# BitBeacon.net
KiCad netlist of a schematic drawn in EAGLE
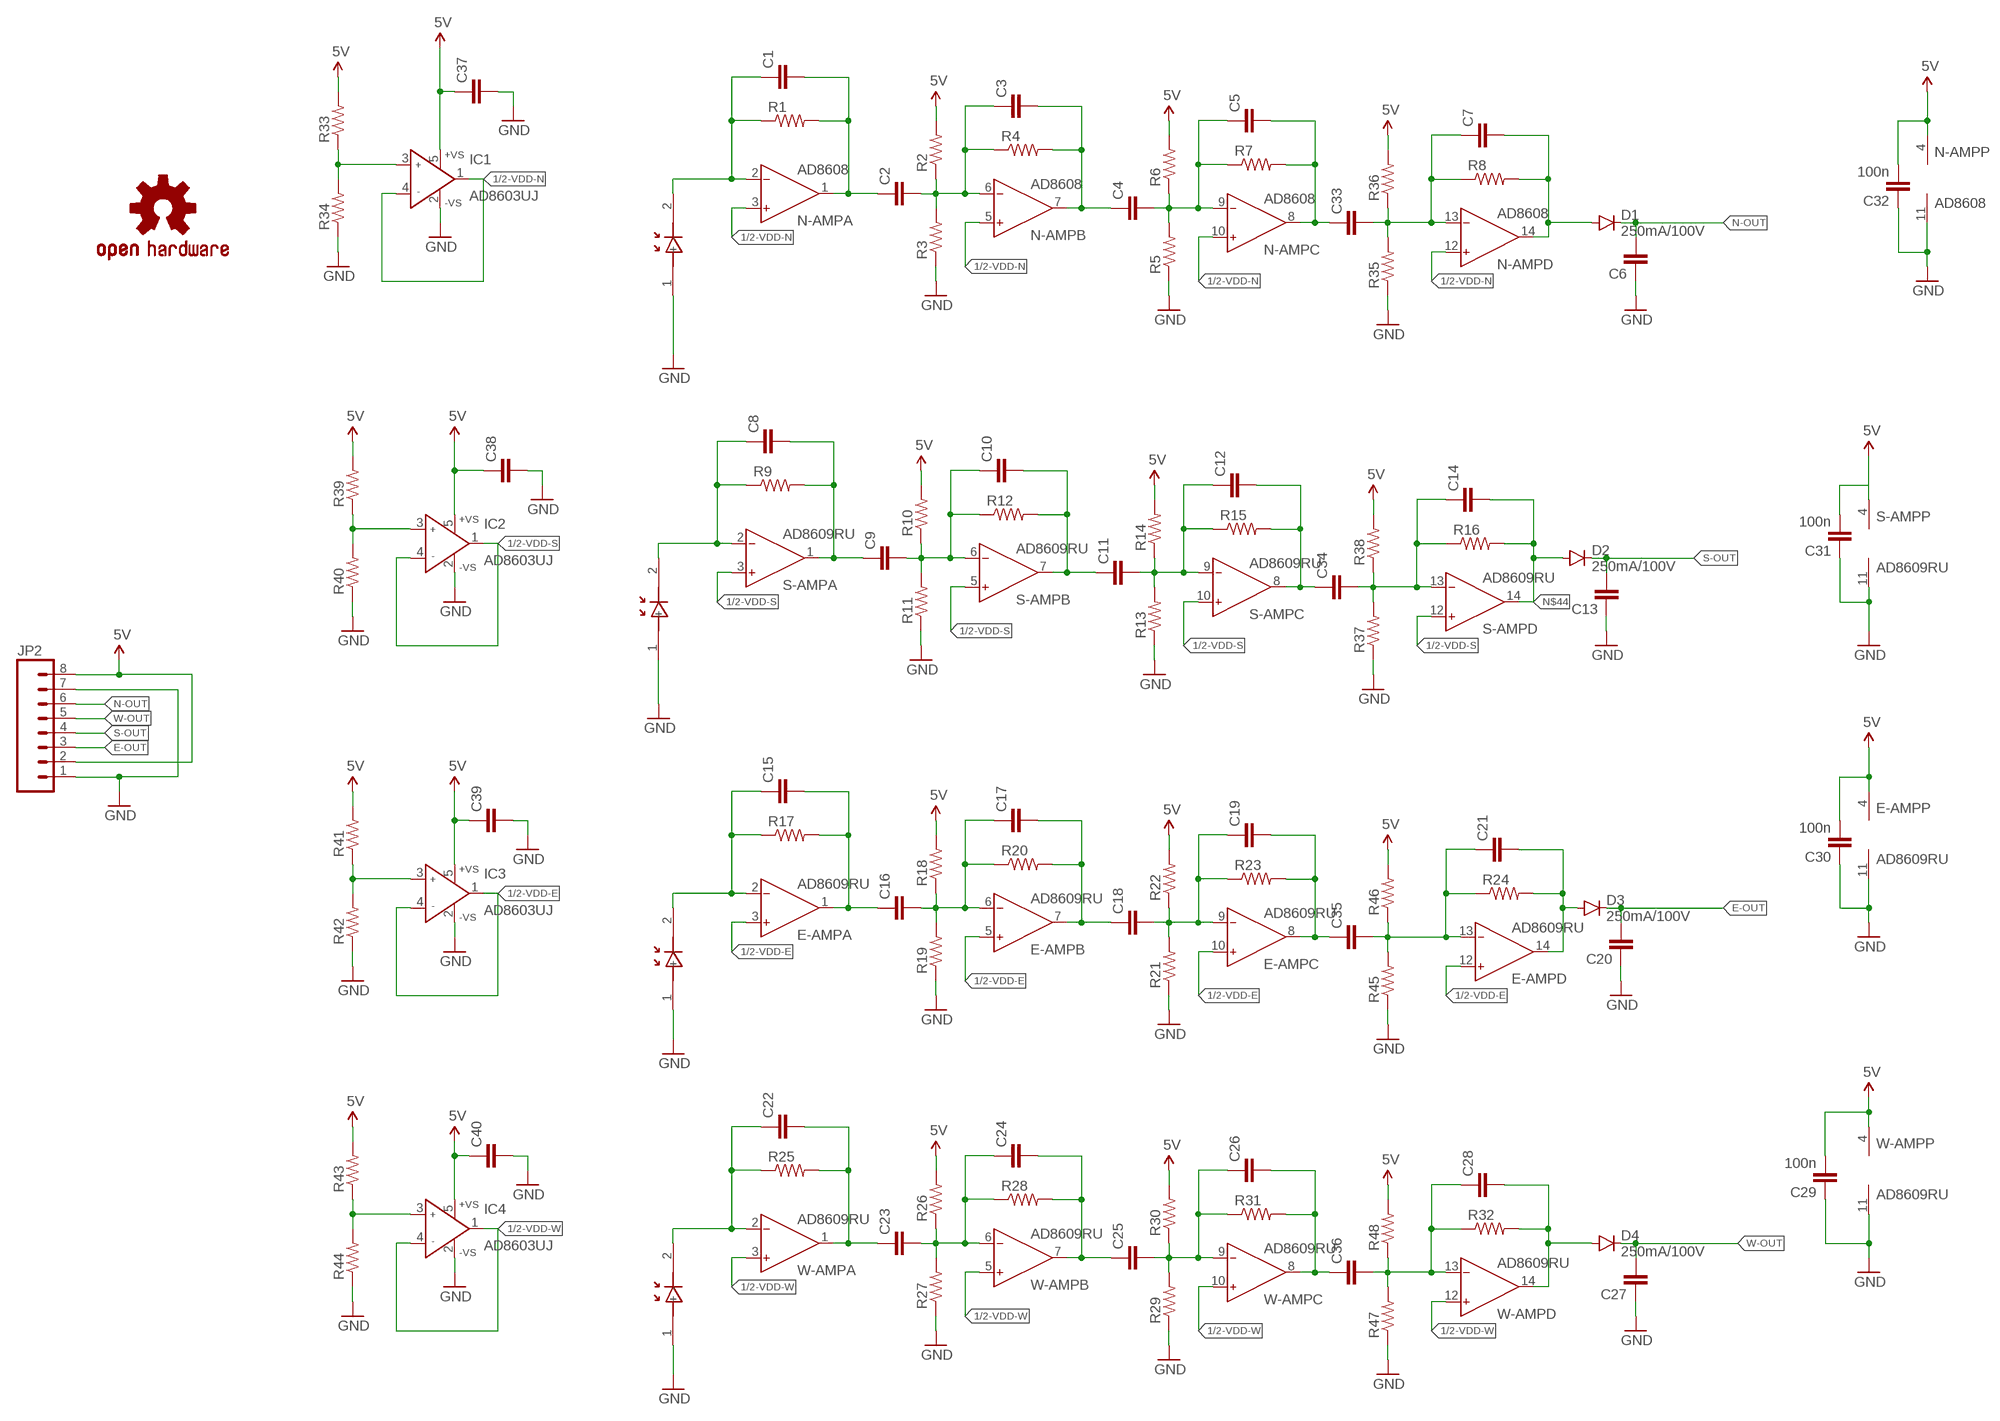
[diagram p0: schematic, sheet 1]

(export (version "E")
  (design (tool "Eeschema 10.0.6"))
  (components
    (comp (ref "C1")
      (value "C-EUC0402")
      (footprint "eagle-import:C0402")
      (libsource (lib "eagle-import") (part "C-EUC0402"))
    )
    (comp (ref "C2")
      (value "C-EUC0402")
      (footprint "eagle-import:C0402")
      (libsource (lib "eagle-import") (part "C-EUC0402"))
    )
    (comp (ref "C3")
      (value "C-EUC0402")
      (footprint "eagle-import:C0402")
      (libsource (lib "eagle-import") (part "C-EUC0402"))
    )
    (comp (ref "C4")
      (value "C-EUC0402")
      (footprint "eagle-import:C0402")
      (libsource (lib "eagle-import") (part "C-EUC0402"))
    )
    (comp (ref "C5")
      (value "C-EUC0402")
      (footprint "eagle-import:C0402")
      (libsource (lib "eagle-import") (part "C-EUC0402"))
    )
    (comp (ref "C6")
      (value "C-EUC0402")
      (footprint "eagle-import:C0402")
      (libsource (lib "eagle-import") (part "C-EUC0402"))
    )
    (comp (ref "C7")
      (value "C-EUC0402")
      (footprint "eagle-import:C0402")
      (libsource (lib "eagle-import") (part "C-EUC0402"))
    )
    (comp (ref "C8")
      (value "C-EUC0402")
      (footprint "eagle-import:C0402")
      (libsource (lib "eagle-import") (part "C-EUC0402"))
    )
    (comp (ref "C9")
      (value "C-EUC0402")
      (footprint "eagle-import:C0402")
      (libsource (lib "eagle-import") (part "C-EUC0402"))
    )
    (comp (ref "C10")
      (value "C-EUC0402")
      (footprint "eagle-import:C0402")
      (libsource (lib "eagle-import") (part "C-EUC0402"))
    )
    (comp (ref "C11")
      (value "C-EUC0402")
      (footprint "eagle-import:C0402")
      (libsource (lib "eagle-import") (part "C-EUC0402"))
    )
    (comp (ref "C12")
      (value "C-EUC0402")
      (footprint "eagle-import:C0402")
      (libsource (lib "eagle-import") (part "C-EUC0402"))
    )
    (comp (ref "C13")
      (value "C-EUC0402")
      (footprint "eagle-import:C0402")
      (libsource (lib "eagle-import") (part "C-EUC0402"))
    )
    (comp (ref "C14")
      (value "C-EUC0402")
      (footprint "eagle-import:C0402")
      (libsource (lib "eagle-import") (part "C-EUC0402"))
    )
    (comp (ref "C15")
      (value "C-EUC0402")
      (footprint "eagle-import:C0402")
      (libsource (lib "eagle-import") (part "C-EUC0402"))
    )
    (comp (ref "C16")
      (value "C-EUC0402")
      (footprint "eagle-import:C0402")
      (libsource (lib "eagle-import") (part "C-EUC0402"))
    )
    (comp (ref "C17")
      (value "C-EUC0402")
      (footprint "eagle-import:C0402")
      (libsource (lib "eagle-import") (part "C-EUC0402"))
    )
    (comp (ref "C18")
      (value "C-EUC0402")
      (footprint "eagle-import:C0402")
      (libsource (lib "eagle-import") (part "C-EUC0402"))
    )
    (comp (ref "C19")
      (value "C-EUC0402")
      (footprint "eagle-import:C0402")
      (libsource (lib "eagle-import") (part "C-EUC0402"))
    )
    (comp (ref "C20")
      (value "C-EUC0402")
      (footprint "eagle-import:C0402")
      (libsource (lib "eagle-import") (part "C-EUC0402"))
    )
    (comp (ref "C21")
      (value "C-EUC0402")
      (footprint "eagle-import:C0402")
      (libsource (lib "eagle-import") (part "C-EUC0402"))
    )
    (comp (ref "C22")
      (value "C-EUC0402")
      (footprint "eagle-import:C0402")
      (libsource (lib "eagle-import") (part "C-EUC0402"))
    )
    (comp (ref "C23")
      (value "C-EUC0402")
      (footprint "eagle-import:C0402")
      (libsource (lib "eagle-import") (part "C-EUC0402"))
    )
    (comp (ref "C24")
      (value "C-EUC0402")
      (footprint "eagle-import:C0402")
      (libsource (lib "eagle-import") (part "C-EUC0402"))
    )
    (comp (ref "C25")
      (value "C-EUC0402")
      (footprint "eagle-import:C0402")
      (libsource (lib "eagle-import") (part "C-EUC0402"))
    )
    (comp (ref "C26")
      (value "C-EUC0402")
      (footprint "eagle-import:C0402")
      (libsource (lib "eagle-import") (part "C-EUC0402"))
    )
    (comp (ref "C27")
      (value "C-EUC0402")
      (footprint "eagle-import:C0402")
      (libsource (lib "eagle-import") (part "C-EUC0402"))
    )
    (comp (ref "C28")
      (value "C-EUC0402")
      (footprint "eagle-import:C0402")
      (libsource (lib "eagle-import") (part "C-EUC0402"))
    )
    (comp (ref "C29")
      (value "100n")
      (footprint "eagle-import:C0402")
      (libsource (lib "eagle-import") (part "C-EUC0402"))
    )
    (comp (ref "C30")
      (value "100n")
      (footprint "eagle-import:C0402")
      (libsource (lib "eagle-import") (part "C-EUC0402"))
    )
    (comp (ref "C31")
      (value "100n")
      (footprint "eagle-import:C0402")
      (libsource (lib "eagle-import") (part "C-EUC0402"))
    )
    (comp (ref "C32")
      (value "100n")
      (footprint "eagle-import:C0402")
      (libsource (lib "eagle-import") (part "C-EUC0402"))
    )
    (comp (ref "C33")
      (value "C-EUC0402")
      (footprint "eagle-import:C0402")
      (libsource (lib "eagle-import") (part "C-EUC0402"))
    )
    (comp (ref "C34")
      (value "C-EUC0402")
      (footprint "eagle-import:C0402")
      (libsource (lib "eagle-import") (part "C-EUC0402"))
    )
    (comp (ref "C35")
      (value "C-EUC0402")
      (footprint "eagle-import:C0402")
      (libsource (lib "eagle-import") (part "C-EUC0402"))
    )
    (comp (ref "C36")
      (value "C-EUC0402")
      (footprint "eagle-import:C0402")
      (libsource (lib "eagle-import") (part "C-EUC0402"))
    )
    (comp (ref "C37")
      (value "C-EUC0402")
      (footprint "eagle-import:C0402")
      (libsource (lib "eagle-import") (part "C-EUC0402"))
    )
    (comp (ref "C38")
      (value "C-EUC0402")
      (footprint "eagle-import:C0402")
      (libsource (lib "eagle-import") (part "C-EUC0402"))
    )
    (comp (ref "C39")
      (value "C-EUC0402")
      (footprint "eagle-import:C0402")
      (libsource (lib "eagle-import") (part "C-EUC0402"))
    )
    (comp (ref "C40")
      (value "C-EUC0402")
      (footprint "eagle-import:C0402")
      (libsource (lib "eagle-import") (part "C-EUC0402"))
    )
    (comp (ref "D1")
      (value "250mA/100V")
      (footprint "eagle-import:SOD-323")
      (libsource (lib "eagle-import") (part "DIODEBAS16"))
    )
    (comp (ref "D2")
      (value "250mA/100V")
      (footprint "eagle-import:SOD-323")
      (libsource (lib "eagle-import") (part "DIODEBAS16"))
    )
    (comp (ref "D3")
      (value "250mA/100V")
      (footprint "eagle-import:SOD-323")
      (libsource (lib "eagle-import") (part "DIODEBAS16"))
    )
    (comp (ref "D4")
      (value "250mA/100V")
      (footprint "eagle-import:SOD-323")
      (libsource (lib "eagle-import") (part "DIODEBAS16"))
    )
    (comp (ref "E-AMP")
      (value "AD8609RU")
      (footprint "eagle-import:TSSOP14")
      (fields (field (name "MF") "ALTERA CORPORATION") (field (name "MPN") "AD8609ARUZ"))
      (libsource (lib "eagle-import") (part "AD8609RU"))
    )
    (comp (ref "E-PD1")
      (value "BPW46")
      (footprint "eagle-import:PIN-PHOTODIODE")
      (libsource (lib "eagle-import") (part "BPW46"))
    )
    (comp (ref "IC1")
      (value "AD8603UJ")
      (footprint "eagle-import:SOT23-5")
      (fields (field (name "MF") "ALTERA CORPORATION") (field (name "MPN") "AD8603AUJZ-REEL7"))
      (libsource (lib "eagle-import") (part "AD8603UJ"))
    )
    (comp (ref "IC2")
      (value "AD8603UJ")
      (footprint "eagle-import:SOT23-5")
      (fields (field (name "MF") "ALTERA CORPORATION") (field (name "MPN") "AD8603AUJZ-REEL7"))
      (libsource (lib "eagle-import") (part "AD8603UJ"))
    )
    (comp (ref "IC3")
      (value "AD8603UJ")
      (footprint "eagle-import:SOT23-5")
      (fields (field (name "MF") "ALTERA CORPORATION") (field (name "MPN") "AD8603AUJZ-REEL7"))
      (libsource (lib "eagle-import") (part "AD8603UJ"))
    )
    (comp (ref "IC4")
      (value "AD8603UJ")
      (footprint "eagle-import:SOT23-5")
      (fields (field (name "MF") "ALTERA CORPORATION") (field (name "MPN") "AD8603AUJZ-REEL7"))
      (libsource (lib "eagle-import") (part "AD8603UJ"))
    )
    (comp (ref "JP2")
      (value "M08NO_SILK")
      (footprint "eagle-import:1X08_PIN1_NO_SILK")
      (libsource (lib "eagle-import") (part "M08NO_SILK"))
    )
    (comp (ref "LOGO1")
      (value "OSHW-LOGOS")
      (footprint "eagle-import:OSHW-LOGO-S")
      (libsource (lib "eagle-import") (part "OSHW-LOGOS"))
    )
    (comp (ref "N-AMP")
      (value "AD8608")
      (footprint "eagle-import:TSSOP14")
      (fields (field (name "MF") "ALTERA CORPORATION") (field (name "MPN") "AD8609ARUZ"))
      (libsource (lib "eagle-import") (part "AD8609RU"))
    )
    (comp (ref "N-PD1")
      (value "BPW46")
      (footprint "eagle-import:PIN-PHOTODIODE")
      (libsource (lib "eagle-import") (part "BPW46"))
    )
    (comp (ref "R1")
      (value "R-US_R0402")
      (footprint "eagle-import:R0402")
      (libsource (lib "eagle-import") (part "R-US_R0402"))
    )
    (comp (ref "R2")
      (value "R-US_R0402")
      (footprint "eagle-import:R0402")
      (libsource (lib "eagle-import") (part "R-US_R0402"))
    )
    (comp (ref "R3")
      (value "R-US_R0402")
      (footprint "eagle-import:R0402")
      (libsource (lib "eagle-import") (part "R-US_R0402"))
    )
    (comp (ref "R4")
      (value "R-US_R0402")
      (footprint "eagle-import:R0402")
      (libsource (lib "eagle-import") (part "R-US_R0402"))
    )
    (comp (ref "R5")
      (value "R-US_R0402")
      (footprint "eagle-import:R0402")
      (libsource (lib "eagle-import") (part "R-US_R0402"))
    )
    (comp (ref "R6")
      (value "R-US_R0402")
      (footprint "eagle-import:R0402")
      (libsource (lib "eagle-import") (part "R-US_R0402"))
    )
    (comp (ref "R7")
      (value "R-US_R0402")
      (footprint "eagle-import:R0402")
      (libsource (lib "eagle-import") (part "R-US_R0402"))
    )
    (comp (ref "R8")
      (value "R-US_R0402")
      (footprint "eagle-import:R0402")
      (libsource (lib "eagle-import") (part "R-US_R0402"))
    )
    (comp (ref "R9")
      (value "R-US_R0402")
      (footprint "eagle-import:R0402")
      (libsource (lib "eagle-import") (part "R-US_R0402"))
    )
    (comp (ref "R10")
      (value "R-US_R0402")
      (footprint "eagle-import:R0402")
      (libsource (lib "eagle-import") (part "R-US_R0402"))
    )
    (comp (ref "R11")
      (value "R-US_R0402")
      (footprint "eagle-import:R0402")
      (libsource (lib "eagle-import") (part "R-US_R0402"))
    )
    (comp (ref "R12")
      (value "R-US_R0402")
      (footprint "eagle-import:R0402")
      (libsource (lib "eagle-import") (part "R-US_R0402"))
    )
    (comp (ref "R13")
      (value "R-US_R0402")
      (footprint "eagle-import:R0402")
      (libsource (lib "eagle-import") (part "R-US_R0402"))
    )
    (comp (ref "R14")
      (value "R-US_R0402")
      (footprint "eagle-import:R0402")
      (libsource (lib "eagle-import") (part "R-US_R0402"))
    )
    (comp (ref "R15")
      (value "R-US_R0402")
      (footprint "eagle-import:R0402")
      (libsource (lib "eagle-import") (part "R-US_R0402"))
    )
    (comp (ref "R16")
      (value "R-US_R0402")
      (footprint "eagle-import:R0402")
      (libsource (lib "eagle-import") (part "R-US_R0402"))
    )
    (comp (ref "R17")
      (value "R-US_R0402")
      (footprint "eagle-import:R0402")
      (libsource (lib "eagle-import") (part "R-US_R0402"))
    )
    (comp (ref "R18")
      (value "R-US_R0402")
      (footprint "eagle-import:R0402")
      (libsource (lib "eagle-import") (part "R-US_R0402"))
    )
    (comp (ref "R19")
      (value "R-US_R0402")
      (footprint "eagle-import:R0402")
      (libsource (lib "eagle-import") (part "R-US_R0402"))
    )
    (comp (ref "R20")
      (value "R-US_R0402")
      (footprint "eagle-import:R0402")
      (libsource (lib "eagle-import") (part "R-US_R0402"))
    )
    (comp (ref "R21")
      (value "R-US_R0402")
      (footprint "eagle-import:R0402")
      (libsource (lib "eagle-import") (part "R-US_R0402"))
    )
    (comp (ref "R22")
      (value "R-US_R0402")
      (footprint "eagle-import:R0402")
      (libsource (lib "eagle-import") (part "R-US_R0402"))
    )
    (comp (ref "R23")
      (value "R-US_R0402")
      (footprint "eagle-import:R0402")
      (libsource (lib "eagle-import") (part "R-US_R0402"))
    )
    (comp (ref "R24")
      (value "R-US_R0402")
      (footprint "eagle-import:R0402")
      (libsource (lib "eagle-import") (part "R-US_R0402"))
    )
    (comp (ref "R25")
      (value "R-US_R0402")
      (footprint "eagle-import:R0402")
      (libsource (lib "eagle-import") (part "R-US_R0402"))
    )
    (comp (ref "R26")
      (value "R-US_R0402")
      (footprint "eagle-import:R0402")
      (libsource (lib "eagle-import") (part "R-US_R0402"))
    )
    (comp (ref "R27")
      (value "R-US_R0402")
      (footprint "eagle-import:R0402")
      (libsource (lib "eagle-import") (part "R-US_R0402"))
    )
    (comp (ref "R28")
      (value "R-US_R0402")
      (footprint "eagle-import:R0402")
      (libsource (lib "eagle-import") (part "R-US_R0402"))
    )
    (comp (ref "R29")
      (value "R-US_R0402")
      (footprint "eagle-import:R0402")
      (libsource (lib "eagle-import") (part "R-US_R0402"))
    )
    (comp (ref "R30")
      (value "R-US_R0402")
      (footprint "eagle-import:R0402")
      (libsource (lib "eagle-import") (part "R-US_R0402"))
    )
    (comp (ref "R31")
      (value "R-US_R0402")
      (footprint "eagle-import:R0402")
      (libsource (lib "eagle-import") (part "R-US_R0402"))
    )
    (comp (ref "R32")
      (value "R-US_R0402")
      (footprint "eagle-import:R0402")
      (libsource (lib "eagle-import") (part "R-US_R0402"))
    )
    (comp (ref "R33")
      (value "R-US_R0402")
      (footprint "eagle-import:R0402")
      (libsource (lib "eagle-import") (part "R-US_R0402"))
    )
    (comp (ref "R34")
      (value "R-US_R0402")
      (footprint "eagle-import:R0402")
      (libsource (lib "eagle-import") (part "R-US_R0402"))
    )
    (comp (ref "R35")
      (value "R-US_R0402")
      (footprint "eagle-import:R0402")
      (libsource (lib "eagle-import") (part "R-US_R0402"))
    )
    (comp (ref "R36")
      (value "R-US_R0402")
      (footprint "eagle-import:R0402")
      (libsource (lib "eagle-import") (part "R-US_R0402"))
    )
    (comp (ref "R37")
      (value "R-US_R0402")
      (footprint "eagle-import:R0402")
      (libsource (lib "eagle-import") (part "R-US_R0402"))
    )
    (comp (ref "R38")
      (value "R-US_R0402")
      (footprint "eagle-import:R0402")
      (libsource (lib "eagle-import") (part "R-US_R0402"))
    )
    (comp (ref "R39")
      (value "R-US_R0402")
      (footprint "eagle-import:R0402")
      (libsource (lib "eagle-import") (part "R-US_R0402"))
    )
    (comp (ref "R40")
      (value "R-US_R0402")
      (footprint "eagle-import:R0402")
      (libsource (lib "eagle-import") (part "R-US_R0402"))
    )
    (comp (ref "R41")
      (value "R-US_R0402")
      (footprint "eagle-import:R0402")
      (libsource (lib "eagle-import") (part "R-US_R0402"))
    )
    (comp (ref "R42")
      (value "R-US_R0402")
      (footprint "eagle-import:R0402")
      (libsource (lib "eagle-import") (part "R-US_R0402"))
    )
    (comp (ref "R43")
      (value "R-US_R0402")
      (footprint "eagle-import:R0402")
      (libsource (lib "eagle-import") (part "R-US_R0402"))
    )
    (comp (ref "R44")
      (value "R-US_R0402")
      (footprint "eagle-import:R0402")
      (libsource (lib "eagle-import") (part "R-US_R0402"))
    )
    (comp (ref "R45")
      (value "R-US_R0402")
      (footprint "eagle-import:R0402")
      (libsource (lib "eagle-import") (part "R-US_R0402"))
    )
    (comp (ref "R46")
      (value "R-US_R0402")
      (footprint "eagle-import:R0402")
      (libsource (lib "eagle-import") (part "R-US_R0402"))
    )
    (comp (ref "R47")
      (value "R-US_R0402")
      (footprint "eagle-import:R0402")
      (libsource (lib "eagle-import") (part "R-US_R0402"))
    )
    (comp (ref "R48")
      (value "R-US_R0402")
      (footprint "eagle-import:R0402")
      (libsource (lib "eagle-import") (part "R-US_R0402"))
    )
    (comp (ref "S-AMP")
      (value "AD8609RU")
      (footprint "eagle-import:TSSOP14")
      (fields (field (name "MF") "ALTERA CORPORATION") (field (name "MPN") "AD8609ARUZ"))
      (libsource (lib "eagle-import") (part "AD8609RU"))
    )
    (comp (ref "S-PD1")
      (value "BPW46")
      (footprint "eagle-import:PIN-PHOTODIODE")
      (libsource (lib "eagle-import") (part "BPW46"))
    )
    (comp (ref "W-AMP")
      (value "AD8609RU")
      (footprint "eagle-import:TSSOP14")
      (fields (field (name "MF") "ALTERA CORPORATION") (field (name "MPN") "AD8609ARUZ"))
      (libsource (lib "eagle-import") (part "AD8609RU"))
    )
    (comp (ref "W-PD1")
      (value "BPW46")
      (footprint "eagle-import:PIN-PHOTODIODE")
      (libsource (lib "eagle-import") (part "BPW46"))
    )
  )
  (nets
    (net (code "1") (name "1{slash}2-VDD-E") (class "Default")
      (node (ref "E-AMP") (pin "10") (pinfunction "IN+_10") (pintype "input"))
      (node (ref "E-AMP") (pin "12") (pinfunction "IN+_12") (pintype "input"))
      (node (ref "E-AMP") (pin "3") (pinfunction "IN+_3") (pintype "input"))
      (node (ref "E-AMP") (pin "5") (pinfunction "IN+_5") (pintype "input"))
      (node (ref "IC3") (pin "1") (pinfunction "OUT_1") (pintype "output"))
      (node (ref "IC3") (pin "4") (pinfunction "IN-_4") (pintype "input"))
    )
    (net (code "2") (name "1{slash}2-VDD-N") (class "Default")
      (node (ref "IC1") (pin "1") (pinfunction "OUT_1") (pintype "output"))
      (node (ref "IC1") (pin "4") (pinfunction "IN-_4") (pintype "input"))
      (node (ref "N-AMP") (pin "10") (pinfunction "IN+_10") (pintype "input"))
      (node (ref "N-AMP") (pin "12") (pinfunction "IN+_12") (pintype "input"))
      (node (ref "N-AMP") (pin "3") (pinfunction "IN+_3") (pintype "input"))
      (node (ref "N-AMP") (pin "5") (pinfunction "IN+_5") (pintype "input"))
    )
    (net (code "3") (name "1{slash}2-VDD-S") (class "Default")
      (node (ref "IC2") (pin "1") (pinfunction "OUT_1") (pintype "output"))
      (node (ref "IC2") (pin "4") (pinfunction "IN-_4") (pintype "input"))
      (node (ref "S-AMP") (pin "10") (pinfunction "IN+_10") (pintype "input"))
      (node (ref "S-AMP") (pin "12") (pinfunction "IN+_12") (pintype "input"))
      (node (ref "S-AMP") (pin "3") (pinfunction "IN+_3") (pintype "input"))
      (node (ref "S-AMP") (pin "5") (pinfunction "IN+_5") (pintype "input"))
    )
    (net (code "4") (name "1{slash}2-VDD-W") (class "Default")
      (node (ref "IC4") (pin "1") (pinfunction "OUT_1") (pintype "output"))
      (node (ref "IC4") (pin "4") (pinfunction "IN-_4") (pintype "input"))
      (node (ref "W-AMP") (pin "10") (pinfunction "IN+_10") (pintype "input"))
      (node (ref "W-AMP") (pin "12") (pinfunction "IN+_12") (pintype "input"))
      (node (ref "W-AMP") (pin "3") (pinfunction "IN+_3") (pintype "input"))
      (node (ref "W-AMP") (pin "5") (pinfunction "IN+_5") (pintype "input"))
    )
    (net (code "5") (name "5V") (class "Default")
      (node (ref "C29") (pin "2") (pinfunction "2_2") (pintype "passive"))
      (node (ref "C30") (pin "2") (pinfunction "2_2") (pintype "passive"))
      (node (ref "C31") (pin "2") (pinfunction "2_2") (pintype "passive"))
      (node (ref "C32") (pin "2") (pinfunction "2_2") (pintype "passive"))
      (node (ref "C37") (pin "1") (pinfunction "1_1") (pintype "passive"))
      (node (ref "C38") (pin "1") (pinfunction "1_1") (pintype "passive"))
      (node (ref "C39") (pin "1") (pinfunction "1_1") (pintype "passive"))
      (node (ref "C40") (pin "1") (pinfunction "1_1") (pintype "passive"))
      (node (ref "E-AMP") (pin "4") (pinfunction "V+_4") (pintype "power_in"))
      (node (ref "IC1") (pin "5") (pinfunction "+VS_5") (pintype "input"))
      (node (ref "IC2") (pin "5") (pinfunction "+VS_5") (pintype "input"))
      (node (ref "IC3") (pin "5") (pinfunction "+VS_5") (pintype "input"))
      (node (ref "IC4") (pin "5") (pinfunction "+VS_5") (pintype "input"))
      (node (ref "JP2") (pin "2") (pinfunction "2_2") (pintype "passive"))
      (node (ref "JP2") (pin "8") (pinfunction "8_8") (pintype "passive"))
      (node (ref "N-AMP") (pin "4") (pinfunction "V+_4") (pintype "power_in"))
      (node (ref "R10") (pin "2") (pinfunction "2_2") (pintype "passive"))
      (node (ref "R14") (pin "2") (pinfunction "2_2") (pintype "passive"))
      (node (ref "R18") (pin "2") (pinfunction "2_2") (pintype "passive"))
      (node (ref "R2") (pin "2") (pinfunction "2_2") (pintype "passive"))
      (node (ref "R22") (pin "2") (pinfunction "2_2") (pintype "passive"))
      (node (ref "R26") (pin "2") (pinfunction "2_2") (pintype "passive"))
      (node (ref "R30") (pin "2") (pinfunction "2_2") (pintype "passive"))
      (node (ref "R33") (pin "2") (pinfunction "2_2") (pintype "passive"))
      (node (ref "R36") (pin "2") (pinfunction "2_2") (pintype "passive"))
      (node (ref "R38") (pin "2") (pinfunction "2_2") (pintype "passive"))
      (node (ref "R39") (pin "2") (pinfunction "2_2") (pintype "passive"))
      (node (ref "R41") (pin "2") (pinfunction "2_2") (pintype "passive"))
      (node (ref "R43") (pin "2") (pinfunction "2_2") (pintype "passive"))
      (node (ref "R46") (pin "2") (pinfunction "2_2") (pintype "passive"))
      (node (ref "R48") (pin "2") (pinfunction "2_2") (pintype "passive"))
      (node (ref "R6") (pin "2") (pinfunction "2_2") (pintype "passive"))
      (node (ref "S-AMP") (pin "4") (pinfunction "V+_4") (pintype "power_in"))
      (node (ref "W-AMP") (pin "4") (pinfunction "V+_4") (pintype "power_in"))
    )
    (net (code "6") (name "E-OUT") (class "Default")
      (node (ref "C20") (pin "2") (pinfunction "2_2") (pintype "passive"))
      (node (ref "D3") (pin "C") (pinfunction "C_C") (pintype "passive"))
      (node (ref "JP2") (pin "3") (pinfunction "3_3") (pintype "passive"))
    )
    (net (code "7") (name "GND") (class "Default")
      (node (ref "C13") (pin "1") (pinfunction "1_1") (pintype "passive"))
      (node (ref "C20") (pin "1") (pinfunction "1_1") (pintype "passive"))
      (node (ref "C27") (pin "1") (pinfunction "1_1") (pintype "passive"))
      (node (ref "C29") (pin "1") (pinfunction "1_1") (pintype "passive"))
      (node (ref "C30") (pin "1") (pinfunction "1_1") (pintype "passive"))
      (node (ref "C31") (pin "1") (pinfunction "1_1") (pintype "passive"))
      (node (ref "C32") (pin "1") (pinfunction "1_1") (pintype "passive"))
      (node (ref "C37") (pin "2") (pinfunction "2_2") (pintype "passive"))
      (node (ref "C38") (pin "2") (pinfunction "2_2") (pintype "passive"))
      (node (ref "C39") (pin "2") (pinfunction "2_2") (pintype "passive"))
      (node (ref "C40") (pin "2") (pinfunction "2_2") (pintype "passive"))
      (node (ref "C6") (pin "1") (pinfunction "1_1") (pintype "passive"))
      (node (ref "E-AMP") (pin "11") (pinfunction "V-_11") (pintype "power_in"))
      (node (ref "E-PD1") (pin "1") (pinfunction "+_1") (pintype "bidirectional"))
      (node (ref "IC1") (pin "2") (pinfunction "-VS_2") (pintype "input"))
      (node (ref "IC2") (pin "2") (pinfunction "-VS_2") (pintype "input"))
      (node (ref "IC3") (pin "2") (pinfunction "-VS_2") (pintype "input"))
      (node (ref "IC4") (pin "2") (pinfunction "-VS_2") (pintype "input"))
      (node (ref "JP2") (pin "1") (pinfunction "1_1") (pintype "passive"))
      (node (ref "JP2") (pin "7") (pinfunction "7_7") (pintype "passive"))
      (node (ref "N-AMP") (pin "11") (pinfunction "V-_11") (pintype "power_in"))
      (node (ref "N-PD1") (pin "1") (pinfunction "+_1") (pintype "bidirectional"))
      (node (ref "R11") (pin "1") (pinfunction "1_1") (pintype "passive"))
      (node (ref "R13") (pin "1") (pinfunction "1_1") (pintype "passive"))
      (node (ref "R19") (pin "1") (pinfunction "1_1") (pintype "passive"))
      (node (ref "R21") (pin "1") (pinfunction "1_1") (pintype "passive"))
      (node (ref "R27") (pin "1") (pinfunction "1_1") (pintype "passive"))
      (node (ref "R29") (pin "1") (pinfunction "1_1") (pintype "passive"))
      (node (ref "R3") (pin "1") (pinfunction "1_1") (pintype "passive"))
      (node (ref "R34") (pin "1") (pinfunction "1_1") (pintype "passive"))
      (node (ref "R35") (pin "1") (pinfunction "1_1") (pintype "passive"))
      (node (ref "R37") (pin "1") (pinfunction "1_1") (pintype "passive"))
      (node (ref "R40") (pin "1") (pinfunction "1_1") (pintype "passive"))
      (node (ref "R42") (pin "1") (pinfunction "1_1") (pintype "passive"))
      (node (ref "R44") (pin "1") (pinfunction "1_1") (pintype "passive"))
      (node (ref "R45") (pin "1") (pinfunction "1_1") (pintype "passive"))
      (node (ref "R47") (pin "1") (pinfunction "1_1") (pintype "passive"))
      (node (ref "R5") (pin "1") (pinfunction "1_1") (pintype "passive"))
      (node (ref "S-AMP") (pin "11") (pinfunction "V-_11") (pintype "power_in"))
      (node (ref "S-PD1") (pin "1") (pinfunction "+_1") (pintype "bidirectional"))
      (node (ref "W-AMP") (pin "11") (pinfunction "V-_11") (pintype "power_in"))
      (node (ref "W-PD1") (pin "1") (pinfunction "+_1") (pintype "bidirectional"))
    )
    (net (code "8") (name "N$44") (class "Default")
      (node (ref "C14") (pin "2") (pinfunction "2_2") (pintype "passive"))
      (node (ref "D2") (pin "A") (pinfunction "A_A") (pintype "passive"))
      (node (ref "R16") (pin "2") (pinfunction "2_2") (pintype "passive"))
      (node (ref "S-AMP") (pin "14") (pinfunction "OUT_14") (pintype "output"))
    )
    (net (code "9") (name "N-OUT") (class "Default")
      (node (ref "C6") (pin "2") (pinfunction "2_2") (pintype "passive"))
      (node (ref "D1") (pin "C") (pinfunction "C_C") (pintype "passive"))
      (node (ref "JP2") (pin "6") (pinfunction "6_6") (pintype "passive"))
    )
    (net (code "10") (name "Net-(E-AMPA-IN-)") (class "Default")
      (node (ref "C15") (pin "1") (pinfunction "1_1") (pintype "passive"))
      (node (ref "E-AMP") (pin "2") (pinfunction "IN-_2") (pintype "input"))
      (node (ref "E-PD1") (pin "2") (pinfunction "-_2") (pintype "bidirectional"))
      (node (ref "R17") (pin "1") (pinfunction "1_1") (pintype "passive"))
    )
    (net (code "11") (name "Net-(E-AMPA-OUT)") (class "Default")
      (node (ref "C15") (pin "2") (pinfunction "2_2") (pintype "passive"))
      (node (ref "C16") (pin "1") (pinfunction "1_1") (pintype "passive"))
      (node (ref "E-AMP") (pin "1") (pinfunction "OUT_1") (pintype "output"))
      (node (ref "R17") (pin "2") (pinfunction "2_2") (pintype "passive"))
    )
    (net (code "12") (name "Net-(E-AMPB-IN-)") (class "Default")
      (node (ref "C16") (pin "2") (pinfunction "2_2") (pintype "passive"))
      (node (ref "C17") (pin "1") (pinfunction "1_1") (pintype "passive"))
      (node (ref "E-AMP") (pin "6") (pinfunction "IN-_6") (pintype "input"))
      (node (ref "R18") (pin "1") (pinfunction "1_1") (pintype "passive"))
      (node (ref "R19") (pin "2") (pinfunction "2_2") (pintype "passive"))
      (node (ref "R20") (pin "1") (pinfunction "1_1") (pintype "passive"))
    )
    (net (code "13") (name "Net-(E-AMPB-OUT)") (class "Default")
      (node (ref "C17") (pin "2") (pinfunction "2_2") (pintype "passive"))
      (node (ref "C18") (pin "1") (pinfunction "1_1") (pintype "passive"))
      (node (ref "E-AMP") (pin "7") (pinfunction "OUT_7") (pintype "output"))
      (node (ref "R20") (pin "2") (pinfunction "2_2") (pintype "passive"))
    )
    (net (code "14") (name "Net-(E-AMPC-IN-)") (class "Default")
      (node (ref "C18") (pin "2") (pinfunction "2_2") (pintype "passive"))
      (node (ref "C19") (pin "1") (pinfunction "1_1") (pintype "passive"))
      (node (ref "E-AMP") (pin "9") (pinfunction "IN-_9") (pintype "input"))
      (node (ref "R21") (pin "2") (pinfunction "2_2") (pintype "passive"))
      (node (ref "R22") (pin "1") (pinfunction "1_1") (pintype "passive"))
      (node (ref "R23") (pin "1") (pinfunction "1_1") (pintype "passive"))
    )
    (net (code "15") (name "Net-(E-AMPC-OUT)") (class "Default")
      (node (ref "C19") (pin "2") (pinfunction "2_2") (pintype "passive"))
      (node (ref "C35") (pin "1") (pinfunction "1_1") (pintype "passive"))
      (node (ref "E-AMP") (pin "8") (pinfunction "OUT_8") (pintype "output"))
      (node (ref "R23") (pin "2") (pinfunction "2_2") (pintype "passive"))
    )
    (net (code "16") (name "Net-(E-AMPD-IN-)") (class "Default")
      (node (ref "C21") (pin "1") (pinfunction "1_1") (pintype "passive"))
      (node (ref "C35") (pin "2") (pinfunction "2_2") (pintype "passive"))
      (node (ref "E-AMP") (pin "13") (pinfunction "IN-_13") (pintype "input"))
      (node (ref "R24") (pin "1") (pinfunction "1_1") (pintype "passive"))
      (node (ref "R45") (pin "2") (pinfunction "2_2") (pintype "passive"))
      (node (ref "R46") (pin "1") (pinfunction "1_1") (pintype "passive"))
    )
    (net (code "17") (name "Net-(E-AMPD-OUT)") (class "Default")
      (node (ref "C21") (pin "2") (pinfunction "2_2") (pintype "passive"))
      (node (ref "D3") (pin "A") (pinfunction "A_A") (pintype "passive"))
      (node (ref "E-AMP") (pin "14") (pinfunction "OUT_14") (pintype "output"))
      (node (ref "R24") (pin "2") (pinfunction "2_2") (pintype "passive"))
    )
    (net (code "18") (name "Net-(IC1-IN+)") (class "Default")
      (node (ref "IC1") (pin "3") (pinfunction "IN+_3") (pintype "input"))
      (node (ref "R33") (pin "1") (pinfunction "1_1") (pintype "passive"))
      (node (ref "R34") (pin "2") (pinfunction "2_2") (pintype "passive"))
    )
    (net (code "19") (name "Net-(IC2-IN+)") (class "Default")
      (node (ref "IC2") (pin "3") (pinfunction "IN+_3") (pintype "input"))
      (node (ref "R39") (pin "1") (pinfunction "1_1") (pintype "passive"))
      (node (ref "R40") (pin "2") (pinfunction "2_2") (pintype "passive"))
    )
    (net (code "20") (name "Net-(IC3-IN+)") (class "Default")
      (node (ref "IC3") (pin "3") (pinfunction "IN+_3") (pintype "input"))
      (node (ref "R41") (pin "1") (pinfunction "1_1") (pintype "passive"))
      (node (ref "R42") (pin "2") (pinfunction "2_2") (pintype "passive"))
    )
    (net (code "21") (name "Net-(IC4-IN+)") (class "Default")
      (node (ref "IC4") (pin "3") (pinfunction "IN+_3") (pintype "input"))
      (node (ref "R43") (pin "1") (pinfunction "1_1") (pintype "passive"))
      (node (ref "R44") (pin "2") (pinfunction "2_2") (pintype "passive"))
    )
    (net (code "22") (name "Net-(N-AMPA-IN-)") (class "Default")
      (node (ref "C1") (pin "1") (pinfunction "1_1") (pintype "passive"))
      (node (ref "N-AMP") (pin "2") (pinfunction "IN-_2") (pintype "input"))
      (node (ref "N-PD1") (pin "2") (pinfunction "-_2") (pintype "bidirectional"))
      (node (ref "R1") (pin "1") (pinfunction "1_1") (pintype "passive"))
    )
    (net (code "23") (name "Net-(N-AMPA-OUT)") (class "Default")
      (node (ref "C1") (pin "2") (pinfunction "2_2") (pintype "passive"))
      (node (ref "C2") (pin "1") (pinfunction "1_1") (pintype "passive"))
      (node (ref "N-AMP") (pin "1") (pinfunction "OUT_1") (pintype "output"))
      (node (ref "R1") (pin "2") (pinfunction "2_2") (pintype "passive"))
    )
    (net (code "24") (name "Net-(N-AMPB-IN-)") (class "Default")
      (node (ref "C2") (pin "2") (pinfunction "2_2") (pintype "passive"))
      (node (ref "C3") (pin "1") (pinfunction "1_1") (pintype "passive"))
      (node (ref "N-AMP") (pin "6") (pinfunction "IN-_6") (pintype "input"))
      (node (ref "R2") (pin "1") (pinfunction "1_1") (pintype "passive"))
      (node (ref "R3") (pin "2") (pinfunction "2_2") (pintype "passive"))
      (node (ref "R4") (pin "1") (pinfunction "1_1") (pintype "passive"))
    )
    (net (code "25") (name "Net-(N-AMPB-OUT)") (class "Default")
      (node (ref "C3") (pin "2") (pinfunction "2_2") (pintype "passive"))
      (node (ref "C4") (pin "1") (pinfunction "1_1") (pintype "passive"))
      (node (ref "N-AMP") (pin "7") (pinfunction "OUT_7") (pintype "output"))
      (node (ref "R4") (pin "2") (pinfunction "2_2") (pintype "passive"))
    )
    (net (code "26") (name "Net-(N-AMPC-IN-)") (class "Default")
      (node (ref "C4") (pin "2") (pinfunction "2_2") (pintype "passive"))
      (node (ref "C5") (pin "1") (pinfunction "1_1") (pintype "passive"))
      (node (ref "N-AMP") (pin "9") (pinfunction "IN-_9") (pintype "input"))
      (node (ref "R5") (pin "2") (pinfunction "2_2") (pintype "passive"))
      (node (ref "R6") (pin "1") (pinfunction "1_1") (pintype "passive"))
      (node (ref "R7") (pin "1") (pinfunction "1_1") (pintype "passive"))
    )
    (net (code "27") (name "Net-(N-AMPC-OUT)") (class "Default")
      (node (ref "C33") (pin "1") (pinfunction "1_1") (pintype "passive"))
      (node (ref "C5") (pin "2") (pinfunction "2_2") (pintype "passive"))
      (node (ref "N-AMP") (pin "8") (pinfunction "OUT_8") (pintype "output"))
      (node (ref "R7") (pin "2") (pinfunction "2_2") (pintype "passive"))
    )
    (net (code "28") (name "Net-(N-AMPD-IN-)") (class "Default")
      (node (ref "C33") (pin "2") (pinfunction "2_2") (pintype "passive"))
      (node (ref "C7") (pin "1") (pinfunction "1_1") (pintype "passive"))
      (node (ref "N-AMP") (pin "13") (pinfunction "IN-_13") (pintype "input"))
      (node (ref "R35") (pin "2") (pinfunction "2_2") (pintype "passive"))
      (node (ref "R36") (pin "1") (pinfunction "1_1") (pintype "passive"))
      (node (ref "R8") (pin "1") (pinfunction "1_1") (pintype "passive"))
    )
    (net (code "29") (name "Net-(N-AMPD-OUT)") (class "Default")
      (node (ref "C7") (pin "2") (pinfunction "2_2") (pintype "passive"))
      (node (ref "D1") (pin "A") (pinfunction "A_A") (pintype "passive"))
      (node (ref "N-AMP") (pin "14") (pinfunction "OUT_14") (pintype "output"))
      (node (ref "R8") (pin "2") (pinfunction "2_2") (pintype "passive"))
    )
    (net (code "30") (name "Net-(S-AMPA-IN-)") (class "Default")
      (node (ref "C8") (pin "1") (pinfunction "1_1") (pintype "passive"))
      (node (ref "R9") (pin "1") (pinfunction "1_1") (pintype "passive"))
      (node (ref "S-AMP") (pin "2") (pinfunction "IN-_2") (pintype "input"))
      (node (ref "S-PD1") (pin "2") (pinfunction "-_2") (pintype "bidirectional"))
    )
    (net (code "31") (name "Net-(S-AMPA-OUT)") (class "Default")
      (node (ref "C8") (pin "2") (pinfunction "2_2") (pintype "passive"))
      (node (ref "C9") (pin "1") (pinfunction "1_1") (pintype "passive"))
      (node (ref "R9") (pin "2") (pinfunction "2_2") (pintype "passive"))
      (node (ref "S-AMP") (pin "1") (pinfunction "OUT_1") (pintype "output"))
    )
    (net (code "32") (name "Net-(S-AMPB-IN-)") (class "Default")
      (node (ref "C10") (pin "1") (pinfunction "1_1") (pintype "passive"))
      (node (ref "C9") (pin "2") (pinfunction "2_2") (pintype "passive"))
      (node (ref "R10") (pin "1") (pinfunction "1_1") (pintype "passive"))
      (node (ref "R11") (pin "2") (pinfunction "2_2") (pintype "passive"))
      (node (ref "R12") (pin "1") (pinfunction "1_1") (pintype "passive"))
      (node (ref "S-AMP") (pin "6") (pinfunction "IN-_6") (pintype "input"))
    )
    (net (code "33") (name "Net-(S-AMPB-OUT)") (class "Default")
      (node (ref "C10") (pin "2") (pinfunction "2_2") (pintype "passive"))
      (node (ref "C11") (pin "1") (pinfunction "1_1") (pintype "passive"))
      (node (ref "R12") (pin "2") (pinfunction "2_2") (pintype "passive"))
      (node (ref "S-AMP") (pin "7") (pinfunction "OUT_7") (pintype "output"))
    )
    (net (code "34") (name "Net-(S-AMPC-IN-)") (class "Default")
      (node (ref "C11") (pin "2") (pinfunction "2_2") (pintype "passive"))
      (node (ref "C12") (pin "1") (pinfunction "1_1") (pintype "passive"))
      (node (ref "R13") (pin "2") (pinfunction "2_2") (pintype "passive"))
      (node (ref "R14") (pin "1") (pinfunction "1_1") (pintype "passive"))
      (node (ref "R15") (pin "1") (pinfunction "1_1") (pintype "passive"))
      (node (ref "S-AMP") (pin "9") (pinfunction "IN-_9") (pintype "input"))
    )
    (net (code "35") (name "Net-(S-AMPC-OUT)") (class "Default")
      (node (ref "C12") (pin "2") (pinfunction "2_2") (pintype "passive"))
      (node (ref "C34") (pin "1") (pinfunction "1_1") (pintype "passive"))
      (node (ref "R15") (pin "2") (pinfunction "2_2") (pintype "passive"))
      (node (ref "S-AMP") (pin "8") (pinfunction "OUT_8") (pintype "output"))
    )
    (net (code "36") (name "Net-(S-AMPD-IN-)") (class "Default")
      (node (ref "C14") (pin "1") (pinfunction "1_1") (pintype "passive"))
      (node (ref "C34") (pin "2") (pinfunction "2_2") (pintype "passive"))
      (node (ref "R16") (pin "1") (pinfunction "1_1") (pintype "passive"))
      (node (ref "R37") (pin "2") (pinfunction "2_2") (pintype "passive"))
      (node (ref "R38") (pin "1") (pinfunction "1_1") (pintype "passive"))
      (node (ref "S-AMP") (pin "13") (pinfunction "IN-_13") (pintype "input"))
    )
    (net (code "37") (name "Net-(W-AMPA-IN-)") (class "Default")
      (node (ref "C22") (pin "1") (pinfunction "1_1") (pintype "passive"))
      (node (ref "R25") (pin "1") (pinfunction "1_1") (pintype "passive"))
      (node (ref "W-AMP") (pin "2") (pinfunction "IN-_2") (pintype "input"))
      (node (ref "W-PD1") (pin "2") (pinfunction "-_2") (pintype "bidirectional"))
    )
    (net (code "38") (name "Net-(W-AMPA-OUT)") (class "Default")
      (node (ref "C22") (pin "2") (pinfunction "2_2") (pintype "passive"))
      (node (ref "C23") (pin "1") (pinfunction "1_1") (pintype "passive"))
      (node (ref "R25") (pin "2") (pinfunction "2_2") (pintype "passive"))
      (node (ref "W-AMP") (pin "1") (pinfunction "OUT_1") (pintype "output"))
    )
    (net (code "39") (name "Net-(W-AMPB-IN-)") (class "Default")
      (node (ref "C23") (pin "2") (pinfunction "2_2") (pintype "passive"))
      (node (ref "C24") (pin "1") (pinfunction "1_1") (pintype "passive"))
      (node (ref "R26") (pin "1") (pinfunction "1_1") (pintype "passive"))
      (node (ref "R27") (pin "2") (pinfunction "2_2") (pintype "passive"))
      (node (ref "R28") (pin "1") (pinfunction "1_1") (pintype "passive"))
      (node (ref "W-AMP") (pin "6") (pinfunction "IN-_6") (pintype "input"))
    )
    (net (code "40") (name "Net-(W-AMPB-OUT)") (class "Default")
      (node (ref "C24") (pin "2") (pinfunction "2_2") (pintype "passive"))
      (node (ref "C25") (pin "1") (pinfunction "1_1") (pintype "passive"))
      (node (ref "R28") (pin "2") (pinfunction "2_2") (pintype "passive"))
      (node (ref "W-AMP") (pin "7") (pinfunction "OUT_7") (pintype "output"))
    )
    (net (code "41") (name "Net-(W-AMPC-IN-)") (class "Default")
      (node (ref "C25") (pin "2") (pinfunction "2_2") (pintype "passive"))
      (node (ref "C26") (pin "1") (pinfunction "1_1") (pintype "passive"))
      (node (ref "R29") (pin "2") (pinfunction "2_2") (pintype "passive"))
      (node (ref "R30") (pin "1") (pinfunction "1_1") (pintype "passive"))
      (node (ref "R31") (pin "1") (pinfunction "1_1") (pintype "passive"))
      (node (ref "W-AMP") (pin "9") (pinfunction "IN-_9") (pintype "input"))
    )
    (net (code "42") (name "Net-(W-AMPC-OUT)") (class "Default")
      (node (ref "C26") (pin "2") (pinfunction "2_2") (pintype "passive"))
      (node (ref "C36") (pin "1") (pinfunction "1_1") (pintype "passive"))
      (node (ref "R31") (pin "2") (pinfunction "2_2") (pintype "passive"))
      (node (ref "W-AMP") (pin "8") (pinfunction "OUT_8") (pintype "output"))
    )
    (net (code "43") (name "Net-(W-AMPD-IN-)") (class "Default")
      (node (ref "C28") (pin "1") (pinfunction "1_1") (pintype "passive"))
      (node (ref "C36") (pin "2") (pinfunction "2_2") (pintype "passive"))
      (node (ref "R32") (pin "1") (pinfunction "1_1") (pintype "passive"))
      (node (ref "R47") (pin "2") (pinfunction "2_2") (pintype "passive"))
      (node (ref "R48") (pin "1") (pinfunction "1_1") (pintype "passive"))
      (node (ref "W-AMP") (pin "13") (pinfunction "IN-_13") (pintype "input"))
    )
    (net (code "44") (name "Net-(W-AMPD-OUT)") (class "Default")
      (node (ref "C28") (pin "2") (pinfunction "2_2") (pintype "passive"))
      (node (ref "D4") (pin "A") (pinfunction "A_A") (pintype "passive"))
      (node (ref "R32") (pin "2") (pinfunction "2_2") (pintype "passive"))
      (node (ref "W-AMP") (pin "14") (pinfunction "OUT_14") (pintype "output"))
    )
    (net (code "45") (name "S-OUT") (class "Default")
      (node (ref "C13") (pin "2") (pinfunction "2_2") (pintype "passive"))
      (node (ref "D2") (pin "C") (pinfunction "C_C") (pintype "passive"))
      (node (ref "JP2") (pin "4") (pinfunction "4_4") (pintype "passive"))
    )
    (net (code "46") (name "W-OUT") (class "Default")
      (node (ref "C27") (pin "2") (pinfunction "2_2") (pintype "passive"))
      (node (ref "D4") (pin "C") (pinfunction "C_C") (pintype "passive"))
      (node (ref "JP2") (pin "5") (pinfunction "5_5") (pintype "passive"))
    )
  )
)
